# Sheet_MPU9150_IMU.net
KiCad netlist of a schematic drawn in Altium Designer
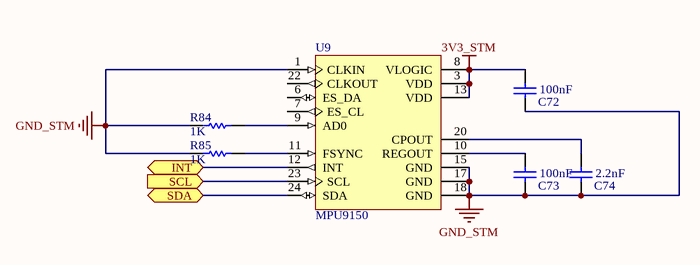
[diagram p0: Sheet_MPU9150_IMU.SchDoc]

(export (version "E")
  (design (tool "Eeschema 10.0.6"))
  (components
    (comp (ref "C72")
      (value "100nF")
      (footprint "1608[0603]")
      (description "Capacitor")
      (libsource (lib "AlmaLib1") (part "Cap_BP"))
    )
    (comp (ref "C73")
      (value "100nF")
      (footprint "1608[0603]")
      (description "Capacitor")
      (libsource (lib "AlmaLib1") (part "Cap_BP"))
    )
    (comp (ref "C74")
      (value "2.2nF")
      (footprint "1608[0603]")
      (description "Capacitor")
      (libsource (lib "AlmaLib1") (part "Cap_BP"))
    )
    (comp (ref "R84")
      (value "1K")
      (footprint "1608[0603]")
      (description "Res")
      (libsource (lib "AlmaLib1") (part "Res"))
    )
    (comp (ref "R85")
      (value "1K")
      (footprint "1608[0603]")
      (description "Res")
      (libsource (lib "AlmaLib1") (part "Res"))
    )
    (comp (ref "U9")
      (value "MPU9150")
      (footprint "QFN24")
      (description "9-DOF IMU")
      (libsource (lib "AlmaLib1") (part "MPU9150"))
    )
  )
  (nets
    (net (code "1") (name "/INT") (class "Default")
      (node (ref "U9") (pin "12") (pinfunction "INT_12") (pintype "output"))
    )
    (net (code "2") (name "/SCL") (class "Default")
      (node (ref "U9") (pin "23") (pinfunction "SCL_23") (pintype "input"))
    )
    (net (code "3") (name "/SDA") (class "Default")
      (node (ref "U9") (pin "24") (pinfunction "SDA_24") (pintype "bidirectional"))
    )
    (net (code "4") (name "3V3_STM") (class "Default")
      (node (ref "C72") (pin "2") (pinfunction "2_2") (pintype "passive"))
      (node (ref "U9") (pin "13") (pinfunction "VDD_13") (pintype "power_in"))
      (node (ref "U9") (pin "3") (pinfunction "VDD_3") (pintype "power_in"))
      (node (ref "U9") (pin "8") (pinfunction "VLOGIC_8") (pintype "power_in"))
    )
    (net (code "5") (name "GND_STM") (class "Default")
      (node (ref "C72") (pin "1") (pinfunction "1_1") (pintype "passive"))
      (node (ref "C73") (pin "1") (pinfunction "1_1") (pintype "passive"))
      (node (ref "C74") (pin "1") (pinfunction "1_1") (pintype "passive"))
      (node (ref "R84") (pin "1") (pinfunction "1_1") (pintype "passive"))
      (node (ref "R85") (pin "1") (pinfunction "1_1") (pintype "passive"))
      (node (ref "U9") (pin "1") (pinfunction "CLKIN_1") (pintype "input"))
      (node (ref "U9") (pin "15") (pinfunction "GND_15") (pintype "power_in"))
      (node (ref "U9") (pin "17") (pinfunction "GND_17") (pintype "power_in"))
      (node (ref "U9") (pin "18") (pinfunction "GND_18") (pintype "power_in"))
    )
    (net (code "6") (name "Net-(U9-AD0)") (class "Default")
      (node (ref "R84") (pin "2") (pinfunction "2_2") (pintype "passive"))
      (node (ref "U9") (pin "9") (pinfunction "AD0_9") (pintype "input"))
    )
    (net (code "7") (name "Net-(U9-CPOUT)") (class "Default")
      (node (ref "C74") (pin "2") (pinfunction "2_2") (pintype "passive"))
      (node (ref "U9") (pin "20") (pinfunction "CPOUT_20") (pintype "passive"))
    )
    (net (code "8") (name "Net-(U9-FSYNC)") (class "Default")
      (node (ref "R85") (pin "2") (pinfunction "2_2") (pintype "passive"))
      (node (ref "U9") (pin "11") (pinfunction "FSYNC_11") (pintype "input"))
    )
    (net (code "9") (name "Net-(U9-REGOUT)") (class "Default")
      (node (ref "C73") (pin "2") (pinfunction "2_2") (pintype "passive"))
      (node (ref "U9") (pin "10") (pinfunction "REGOUT_10") (pintype "power_in"))
    )
    (net (code "10") (name "unconnected-(U9-CLKOUT-Pad22)") (class "Default")
      (node (ref "U9") (pin "22") (pinfunction "CLKOUT_22") (pintype "output"))
    )
    (net (code "11") (name "unconnected-(U9-ES_CL-Pad7)") (class "Default")
      (node (ref "U9") (pin "7") (pinfunction "ES_CL_7") (pintype "output"))
    )
    (net (code "12") (name "unconnected-(U9-ES_DA-Pad6)") (class "Default")
      (node (ref "U9") (pin "6") (pinfunction "ES_DA_6") (pintype "bidirectional"))
    )
  )
)
